# VCA-v2_1.net
KiCad netlist of a schematic drawn in EAGLE
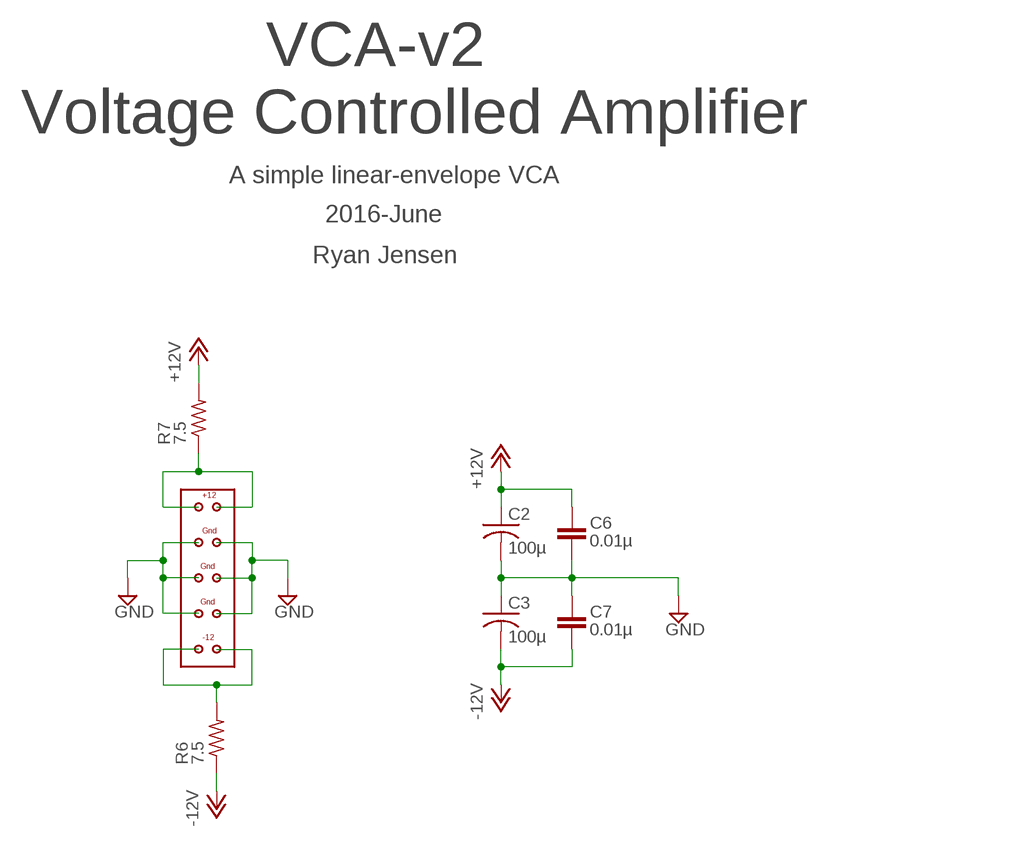
[diagram p0: schematic, sheet 1]
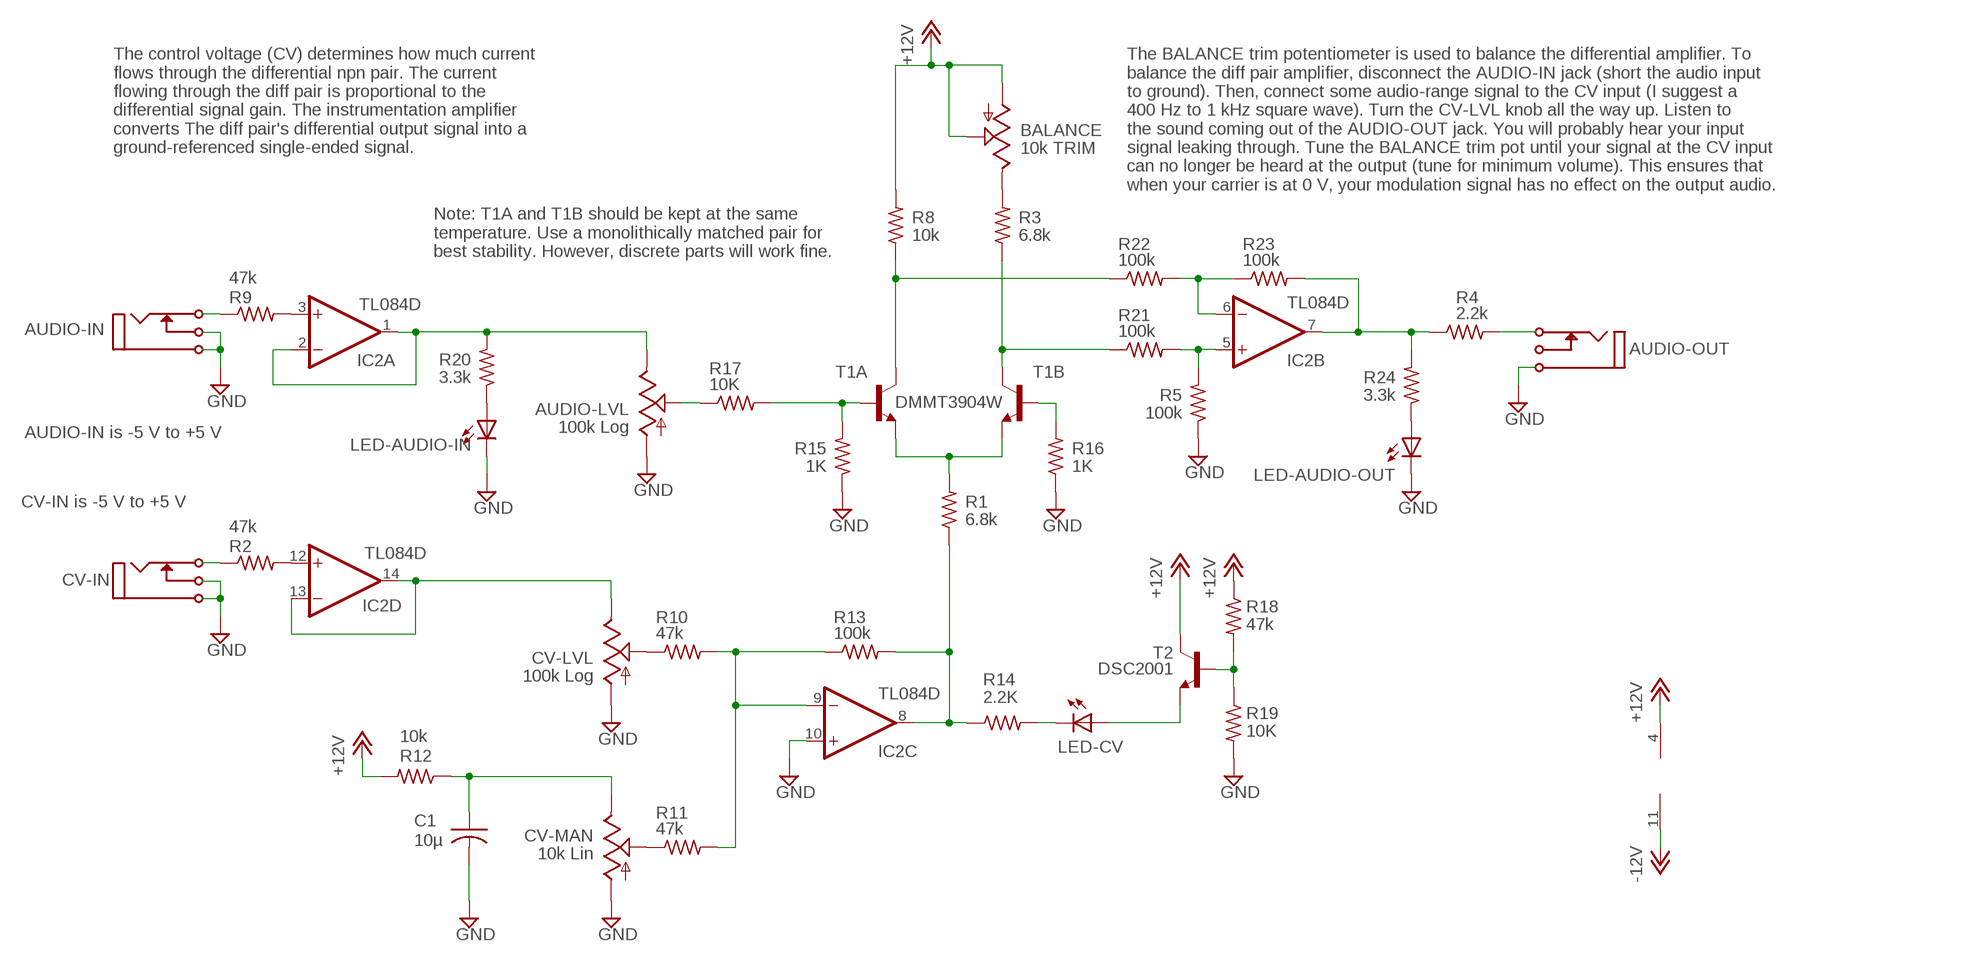
[diagram p1: schematic, sheet 2]

(export (version "E")
  (design (tool "Eeschema 10.0.6"))
  (components
    (comp (ref "AUDIO-IN")
      (value "I/O")
      (footprint "eagle-import:MONO_JACK")
      (libsource (lib "eagle-import") (part "MONO_JACK"))
    )
    (comp (ref "AUDIO-LVL")
      (value "100k Log")
      (footprint "eagle-import:B64Y")
      (libsource (lib "eagle-import") (part "TRIM_US-B64Y"))
    )
    (comp (ref "AUDIO-OUT")
      (value "I/O")
      (footprint "eagle-import:MONO_JACK")
      (libsource (lib "eagle-import") (part "MONO_JACK"))
    )
    (comp (ref "BALANCE")
      (value "10k TRIM")
      (footprint "eagle-import:B64Y")
      (libsource (lib "eagle-import") (part "TRIM_US-B64Y"))
    )
    (comp (ref "C1")
      (value "10µ")
      (footprint "eagle-import:C025-050X050")
      (libsource (lib "eagle-import") (part "C-US025-050X050"))
    )
    (comp (ref "CV-IN")
      (value "I/O")
      (footprint "eagle-import:MONO_JACK")
      (libsource (lib "eagle-import") (part "MONO_JACK"))
    )
    (comp (ref "CV-LVL")
      (value "100k Log")
      (footprint "eagle-import:B64Y")
      (libsource (lib "eagle-import") (part "TRIM_US-B64Y"))
    )
    (comp (ref "CV-MAN")
      (value "10k Lin")
      (footprint "eagle-import:B64Y")
      (libsource (lib "eagle-import") (part "TRIM_US-B64Y"))
    )
    (comp (ref "IC2")
      (value "TL084D")
      (footprint "eagle-import:SO14")
      (libsource (lib "eagle-import") (part "TL084D"))
    )
    (comp (ref "LED-AUDIO-IN")
      (value "TLLG4400")
      (footprint "eagle-import:LED3MM")
      (fields (field (name "MF") "VISHAY SEMICONDUCTOR"))
      (libsource (lib "eagle-import") (part "TLLG4400"))
    )
    (comp (ref "LED-AUDIO-OUT")
      (value "TLLG4400")
      (footprint "eagle-import:LED3MM")
      (fields (field (name "MF") "VISHAY SEMICONDUCTOR"))
      (libsource (lib "eagle-import") (part "TLLG4400"))
    )
    (comp (ref "LED-CV")
      (value "TLLG4400")
      (footprint "eagle-import:LED3MM")
      (fields (field (name "MF") "VISHAY SEMICONDUCTOR"))
      (libsource (lib "eagle-import") (part "TLLG4400"))
    )
    (comp (ref "R1")
      (value "6.8k")
      (footprint "eagle-import:R0603")
      (libsource (lib "eagle-import") (part "R-US_R0603"))
    )
    (comp (ref "R2")
      (value "47k")
      (footprint "eagle-import:R0603")
      (libsource (lib "eagle-import") (part "R-US_R0603"))
    )
    (comp (ref "R3")
      (value "6.8k")
      (footprint "eagle-import:R0603")
      (libsource (lib "eagle-import") (part "R-US_R0603"))
    )
    (comp (ref "R4")
      (value "2.2k")
      (footprint "eagle-import:R0603")
      (libsource (lib "eagle-import") (part "R-US_R0603"))
    )
    (comp (ref "R5")
      (value "100k")
      (footprint "eagle-import:R0603")
      (libsource (lib "eagle-import") (part "R-US_R0603"))
    )
    (comp (ref "R8")
      (value "10k")
      (footprint "eagle-import:R0603")
      (libsource (lib "eagle-import") (part "R-US_R0603"))
    )
    (comp (ref "R9")
      (value "47k")
      (footprint "eagle-import:R0603")
      (libsource (lib "eagle-import") (part "R-US_R0603"))
    )
    (comp (ref "R10")
      (value "47k")
      (footprint "eagle-import:R0603")
      (libsource (lib "eagle-import") (part "R-US_R0603"))
    )
    (comp (ref "R11")
      (value "47k")
      (footprint "eagle-import:R0603")
      (libsource (lib "eagle-import") (part "R-US_R0603"))
    )
    (comp (ref "R12")
      (value "10k")
      (footprint "eagle-import:R0603")
      (libsource (lib "eagle-import") (part "R-US_R0603"))
    )
    (comp (ref "R13")
      (value "100k")
      (footprint "eagle-import:R0603")
      (libsource (lib "eagle-import") (part "R-US_R0603"))
    )
    (comp (ref "R14")
      (value "2.2K")
      (footprint "eagle-import:R0603")
      (libsource (lib "eagle-import") (part "R-US_R0603"))
    )
    (comp (ref "R15")
      (value "1K")
      (footprint "eagle-import:R0603")
      (libsource (lib "eagle-import") (part "R-US_R0603"))
    )
    (comp (ref "R16")
      (value "1K")
      (footprint "eagle-import:R0603")
      (libsource (lib "eagle-import") (part "R-US_R0603"))
    )
    (comp (ref "R17")
      (value "10K")
      (footprint "eagle-import:R0603")
      (libsource (lib "eagle-import") (part "R-US_R0603"))
    )
    (comp (ref "R18")
      (value "47k")
      (footprint "eagle-import:R0603")
      (libsource (lib "eagle-import") (part "R-US_R0603"))
    )
    (comp (ref "R19")
      (value "10K")
      (footprint "eagle-import:R0603")
      (libsource (lib "eagle-import") (part "R-US_R0603"))
    )
    (comp (ref "R20")
      (value "3.3k")
      (footprint "eagle-import:R0603")
      (libsource (lib "eagle-import") (part "R-US_R0603"))
    )
    (comp (ref "R21")
      (value "100k")
      (footprint "eagle-import:R0603")
      (libsource (lib "eagle-import") (part "R-US_R0603"))
    )
    (comp (ref "R22")
      (value "100k")
      (footprint "eagle-import:R0603")
      (libsource (lib "eagle-import") (part "R-US_R0603"))
    )
    (comp (ref "R23")
      (value "100k")
      (footprint "eagle-import:R0603")
      (libsource (lib "eagle-import") (part "R-US_R0603"))
    )
    (comp (ref "R24")
      (value "3.3k")
      (footprint "eagle-import:R0603")
      (libsource (lib "eagle-import") (part "R-US_R0603"))
    )
    (comp (ref "T1")
      (value "DMMT3904W")
      (footprint "eagle-import:SOT363")
      (libsource (lib "eagle-import") (part "DMMT3904W"))
    )
    (comp (ref "T2")
      (value "DSC2001")
      (footprint "eagle-import:SOT23-BEC")
      (libsource (lib "eagle-import") (part "-NPN-SOT23-BECMMBT2222ALT1"))
    )
    (comp (ref "C2")
      (value "100µ")
      (footprint "eagle-import:C025-050X050")
      (libsource (lib "eagle-import") (part "C-US025-050X050"))
    )
    (comp (ref "C3")
      (value "100µ")
      (footprint "eagle-import:C025-050X050")
      (libsource (lib "eagle-import") (part "C-US025-050X050"))
    )
    (comp (ref "C6")
      (value "0.01µ")
      (footprint "eagle-import:C0603")
      (libsource (lib "eagle-import") (part "C-EUC0603"))
    )
    (comp (ref "C7")
      (value "0.01µ")
      (footprint "eagle-import:C0603")
      (libsource (lib "eagle-import") (part "C-EUC0603"))
    )
    (comp (ref "R6")
      (value "7.5")
      (footprint "eagle-import:R0603")
      (libsource (lib "eagle-import") (part "R-US_R0603"))
    )
    (comp (ref "R7")
      (value "7.5")
      (footprint "eagle-import:R0603")
      (libsource (lib "eagle-import") (part "R-US_R0603"))
    )
    (comp (ref "U$1")
      (value "EURORACK-POWER")
      (footprint "eagle-import:EURORACK-POWER")
      (libsource (lib "eagle-import") (part "EURORACK-POWER"))
    )
  )
  (nets
    (net (code "1") (name "+12V") (class "Default")
      (node (ref "BALANCE") (pin "A") (pinfunction "A_A") (pintype "passive"))
      (node (ref "BALANCE") (pin "S") (pinfunction "S_S") (pintype "passive"))
      (node (ref "C2") (pin "1") (pinfunction "1_1") (pintype "passive"))
      (node (ref "C6") (pin "1") (pinfunction "1_1") (pintype "passive"))
      (node (ref "IC2") (pin "4") (pinfunction "V+_4") (pintype "power_in"))
      (node (ref "R12") (pin "2") (pinfunction "2_2") (pintype "passive"))
      (node (ref "R18") (pin "1") (pinfunction "1_1") (pintype "passive"))
      (node (ref "R7") (pin "2") (pinfunction "2_2") (pintype "passive"))
      (node (ref "R8") (pin "2") (pinfunction "2_2") (pintype "passive"))
      (node (ref "T2") (pin "C") (pinfunction "C_C") (pintype "passive"))
    )
    (net (code "2") (name "-12V") (class "Default")
      (node (ref "C3") (pin "2") (pinfunction "2_2") (pintype "passive"))
      (node (ref "C7") (pin "2") (pinfunction "2_2") (pintype "passive"))
      (node (ref "IC2") (pin "11") (pinfunction "V-_11") (pintype "power_in"))
      (node (ref "R6") (pin "1") (pinfunction "1_1") (pintype "passive"))
    )
    (net (code "3") (name "GND") (class "Default")
      (node (ref "AUDIO-IN") (pin "P$1") (pinfunction "P$1_P$1") (pintype "bidirectional"))
      (node (ref "AUDIO-IN") (pin "P$3") (pinfunction "P3_P$3") (pintype "bidirectional"))
      (node (ref "AUDIO-LVL") (pin "A") (pinfunction "A_A") (pintype "passive"))
      (node (ref "AUDIO-OUT") (pin "P$1") (pinfunction "P$1_P$1") (pintype "bidirectional"))
      (node (ref "C1") (pin "2") (pinfunction "2_2") (pintype "passive"))
      (node (ref "C2") (pin "2") (pinfunction "2_2") (pintype "passive"))
      (node (ref "C3") (pin "1") (pinfunction "1_1") (pintype "passive"))
      (node (ref "C6") (pin "2") (pinfunction "2_2") (pintype "passive"))
      (node (ref "C7") (pin "1") (pinfunction "1_1") (pintype "passive"))
      (node (ref "CV-IN") (pin "P$1") (pinfunction "P$1_P$1") (pintype "bidirectional"))
      (node (ref "CV-IN") (pin "P$3") (pinfunction "P3_P$3") (pintype "bidirectional"))
      (node (ref "CV-LVL") (pin "A") (pinfunction "A_A") (pintype "passive"))
      (node (ref "CV-MAN") (pin "A") (pinfunction "A_A") (pintype "passive"))
      (node (ref "IC2") (pin "10") (pinfunction "+IN_10") (pintype "input"))
      (node (ref "LED-AUDIO-IN") (pin "K") (pinfunction "C_K") (pintype "passive"))
      (node (ref "LED-AUDIO-OUT") (pin "K") (pinfunction "C_K") (pintype "passive"))
      (node (ref "R15") (pin "1") (pinfunction "1_1") (pintype "passive"))
      (node (ref "R16") (pin "1") (pinfunction "1_1") (pintype "passive"))
      (node (ref "R19") (pin "2") (pinfunction "2_2") (pintype "passive"))
      (node (ref "R5") (pin "1") (pinfunction "1_1") (pintype "passive"))
      (node (ref "U$1") (pin "P$3") (pinfunction "P$3_P$3") (pintype "bidirectional"))
      (node (ref "U$1") (pin "P$4") (pinfunction "P$4_P$4") (pintype "bidirectional"))
      (node (ref "U$1") (pin "P$5") (pinfunction "P$5_P$5") (pintype "bidirectional"))
      (node (ref "U$1") (pin "P$6") (pinfunction "P$6_P$6") (pintype "bidirectional"))
      (node (ref "U$1") (pin "P$7") (pinfunction "P$7_P$7") (pintype "bidirectional"))
      (node (ref "U$1") (pin "P$8") (pinfunction "P$8_P$8") (pintype "bidirectional"))
    )
    (net (code "4") (name "Net-(AUDIO-IN-P2)") (class "Default")
      (node (ref "AUDIO-IN") (pin "P$2") (pinfunction "P2_P$2") (pintype "bidirectional"))
      (node (ref "R9") (pin "1") (pinfunction "1_1") (pintype "passive"))
    )
    (net (code "5") (name "Net-(AUDIO-LVL-PadS)") (class "Default")
      (node (ref "AUDIO-LVL") (pin "S") (pinfunction "S_S") (pintype "passive"))
      (node (ref "R17") (pin "1") (pinfunction "1_1") (pintype "passive"))
    )
    (net (code "6") (name "Net-(AUDIO-OUT-P2)") (class "Default")
      (node (ref "AUDIO-OUT") (pin "P$2") (pinfunction "P2_P$2") (pintype "bidirectional"))
      (node (ref "R4") (pin "2") (pinfunction "2_2") (pintype "passive"))
    )
    (net (code "7") (name "Net-(BALANCE-PadE)") (class "Default")
      (node (ref "BALANCE") (pin "E") (pinfunction "E_E") (pintype "passive"))
      (node (ref "R3") (pin "2") (pinfunction "2_2") (pintype "passive"))
    )
    (net (code "8") (name "Net-(C1-Pad1)") (class "Default")
      (node (ref "C1") (pin "1") (pinfunction "1_1") (pintype "passive"))
      (node (ref "CV-MAN") (pin "E") (pinfunction "E_E") (pintype "passive"))
      (node (ref "R12") (pin "1") (pinfunction "1_1") (pintype "passive"))
    )
    (net (code "9") (name "Net-(CV-IN-P2)") (class "Default")
      (node (ref "CV-IN") (pin "P$2") (pinfunction "P2_P$2") (pintype "bidirectional"))
      (node (ref "R2") (pin "1") (pinfunction "1_1") (pintype "passive"))
    )
    (net (code "10") (name "Net-(CV-LVL-PadS)") (class "Default")
      (node (ref "CV-LVL") (pin "S") (pinfunction "S_S") (pintype "passive"))
      (node (ref "R10") (pin "1") (pinfunction "1_1") (pintype "passive"))
    )
    (net (code "11") (name "Net-(CV-MAN-PadS)") (class "Default")
      (node (ref "CV-MAN") (pin "S") (pinfunction "S_S") (pintype "passive"))
      (node (ref "R11") (pin "1") (pinfunction "1_1") (pintype "passive"))
    )
    (net (code "12") (name "Net-(IC2A-+IN)") (class "Default")
      (node (ref "IC2") (pin "3") (pinfunction "+IN_3") (pintype "input"))
      (node (ref "R9") (pin "2") (pinfunction "2_2") (pintype "passive"))
    )
    (net (code "13") (name "Net-(IC2A--IN)") (class "Default")
      (node (ref "AUDIO-LVL") (pin "E") (pinfunction "E_E") (pintype "passive"))
      (node (ref "IC2") (pin "1") (pinfunction "OUT_1") (pintype "output"))
      (node (ref "IC2") (pin "2") (pinfunction "-IN_2") (pintype "input"))
      (node (ref "R20") (pin "2") (pinfunction "2_2") (pintype "passive"))
    )
    (net (code "14") (name "Net-(IC2B-+IN)") (class "Default")
      (node (ref "IC2") (pin "5") (pinfunction "+IN_5") (pintype "input"))
      (node (ref "R21") (pin "2") (pinfunction "2_2") (pintype "passive"))
      (node (ref "R5") (pin "2") (pinfunction "2_2") (pintype "passive"))
    )
    (net (code "15") (name "Net-(IC2B--IN)") (class "Default")
      (node (ref "IC2") (pin "6") (pinfunction "-IN_6") (pintype "input"))
      (node (ref "R22") (pin "2") (pinfunction "2_2") (pintype "passive"))
      (node (ref "R23") (pin "1") (pinfunction "1_1") (pintype "passive"))
    )
    (net (code "16") (name "Net-(IC2B-OUT)") (class "Default")
      (node (ref "IC2") (pin "7") (pinfunction "OUT_7") (pintype "output"))
      (node (ref "R23") (pin "2") (pinfunction "2_2") (pintype "passive"))
      (node (ref "R24") (pin "2") (pinfunction "2_2") (pintype "passive"))
      (node (ref "R4") (pin "1") (pinfunction "1_1") (pintype "passive"))
    )
    (net (code "17") (name "Net-(IC2C--IN)") (class "Default")
      (node (ref "IC2") (pin "9") (pinfunction "-IN_9") (pintype "input"))
      (node (ref "R10") (pin "2") (pinfunction "2_2") (pintype "passive"))
      (node (ref "R11") (pin "2") (pinfunction "2_2") (pintype "passive"))
      (node (ref "R13") (pin "1") (pinfunction "1_1") (pintype "passive"))
    )
    (net (code "18") (name "Net-(IC2C-OUT)") (class "Default")
      (node (ref "IC2") (pin "8") (pinfunction "OUT_8") (pintype "output"))
      (node (ref "R1") (pin "1") (pinfunction "1_1") (pintype "passive"))
      (node (ref "R13") (pin "2") (pinfunction "2_2") (pintype "passive"))
      (node (ref "R14") (pin "1") (pinfunction "1_1") (pintype "passive"))
    )
    (net (code "19") (name "Net-(IC2D-+IN)") (class "Default")
      (node (ref "IC2") (pin "12") (pinfunction "+IN_12") (pintype "input"))
      (node (ref "R2") (pin "2") (pinfunction "2_2") (pintype "passive"))
    )
    (net (code "20") (name "Net-(IC2D--IN)") (class "Default")
      (node (ref "CV-LVL") (pin "E") (pinfunction "E_E") (pintype "passive"))
      (node (ref "IC2") (pin "13") (pinfunction "-IN_13") (pintype "input"))
      (node (ref "IC2") (pin "14") (pinfunction "OUT_14") (pintype "output"))
    )
    (net (code "21") (name "Net-(LED-AUDIO-IN-PadA)") (class "Default")
      (node (ref "LED-AUDIO-IN") (pin "A") (pinfunction "A_A") (pintype "passive"))
      (node (ref "R20") (pin "1") (pinfunction "1_1") (pintype "passive"))
    )
    (net (code "22") (name "Net-(LED-AUDIO-OUT-PadA)") (class "Default")
      (node (ref "LED-AUDIO-OUT") (pin "A") (pinfunction "A_A") (pintype "passive"))
      (node (ref "R24") (pin "1") (pinfunction "1_1") (pintype "passive"))
    )
    (net (code "23") (name "Net-(LED-CV-C)") (class "Default")
      (node (ref "LED-CV") (pin "K") (pinfunction "C_K") (pintype "passive"))
      (node (ref "R14") (pin "2") (pinfunction "2_2") (pintype "passive"))
    )
    (net (code "24") (name "Net-(LED-CV-PadA)") (class "Default")
      (node (ref "LED-CV") (pin "A") (pinfunction "A_A") (pintype "passive"))
      (node (ref "T2") (pin "E") (pinfunction "E_E") (pintype "passive"))
    )
    (net (code "25") (name "Net-(R6-Pad2)") (class "Default")
      (node (ref "R6") (pin "2") (pinfunction "2_2") (pintype "passive"))
      (node (ref "U$1") (pin "P$10") (pinfunction "P$10_P$10") (pintype "bidirectional"))
      (node (ref "U$1") (pin "P$9") (pinfunction "P$9_P$9") (pintype "bidirectional"))
    )
    (net (code "26") (name "Net-(R7-Pad1)") (class "Default")
      (node (ref "R7") (pin "1") (pinfunction "1_1") (pintype "passive"))
      (node (ref "U$1") (pin "P$1") (pinfunction "P$1_P$1") (pintype "bidirectional"))
      (node (ref "U$1") (pin "P$2") (pinfunction "P$2_P$2") (pintype "bidirectional"))
    )
    (net (code "27") (name "Net-(R18-Pad2)") (class "Default")
      (node (ref "R18") (pin "2") (pinfunction "2_2") (pintype "passive"))
      (node (ref "R19") (pin "1") (pinfunction "1_1") (pintype "passive"))
      (node (ref "T2") (pin "B") (pinfunction "B_B") (pintype "passive"))
    )
    (net (code "28") (name "Net-(T1A-B)") (class "Default")
      (node (ref "R15") (pin "2") (pinfunction "2_2") (pintype "passive"))
      (node (ref "R17") (pin "2") (pinfunction "2_2") (pintype "passive"))
      (node (ref "T1") (pin "1") (pinfunction "B_1") (pintype "passive"))
    )
    (net (code "29") (name "Net-(T1A-C)") (class "Default")
      (node (ref "R22") (pin "1") (pinfunction "1_1") (pintype "passive"))
      (node (ref "R8") (pin "1") (pinfunction "1_1") (pintype "passive"))
      (node (ref "T1") (pin "6") (pinfunction "C_6") (pintype "passive"))
    )
    (net (code "30") (name "Net-(T1A-E)") (class "Default")
      (node (ref "R1") (pin "2") (pinfunction "2_2") (pintype "passive"))
      (node (ref "T1") (pin "4") (pinfunction "E_4") (pintype "passive"))
      (node (ref "T1") (pin "5") (pinfunction "E_5") (pintype "passive"))
    )
    (net (code "31") (name "Net-(T1B-B)") (class "Default")
      (node (ref "R16") (pin "2") (pinfunction "2_2") (pintype "passive"))
      (node (ref "T1") (pin "2") (pinfunction "B_2") (pintype "passive"))
    )
    (net (code "32") (name "Net-(T1B-C)") (class "Default")
      (node (ref "R21") (pin "1") (pinfunction "1_1") (pintype "passive"))
      (node (ref "R3") (pin "1") (pinfunction "1_1") (pintype "passive"))
      (node (ref "T1") (pin "3") (pinfunction "C_3") (pintype "passive"))
    )
    (net (code "33") (name "unconnected-(AUDIO-OUT-P3-PadP$3)") (class "Default")
      (node (ref "AUDIO-OUT") (pin "P$3") (pinfunction "P3_P$3") (pintype "bidirectional"))
    )
  )
)
